# eBox_ACdetect.net
KiCad netlist of a schematic drawn in Altium Designer
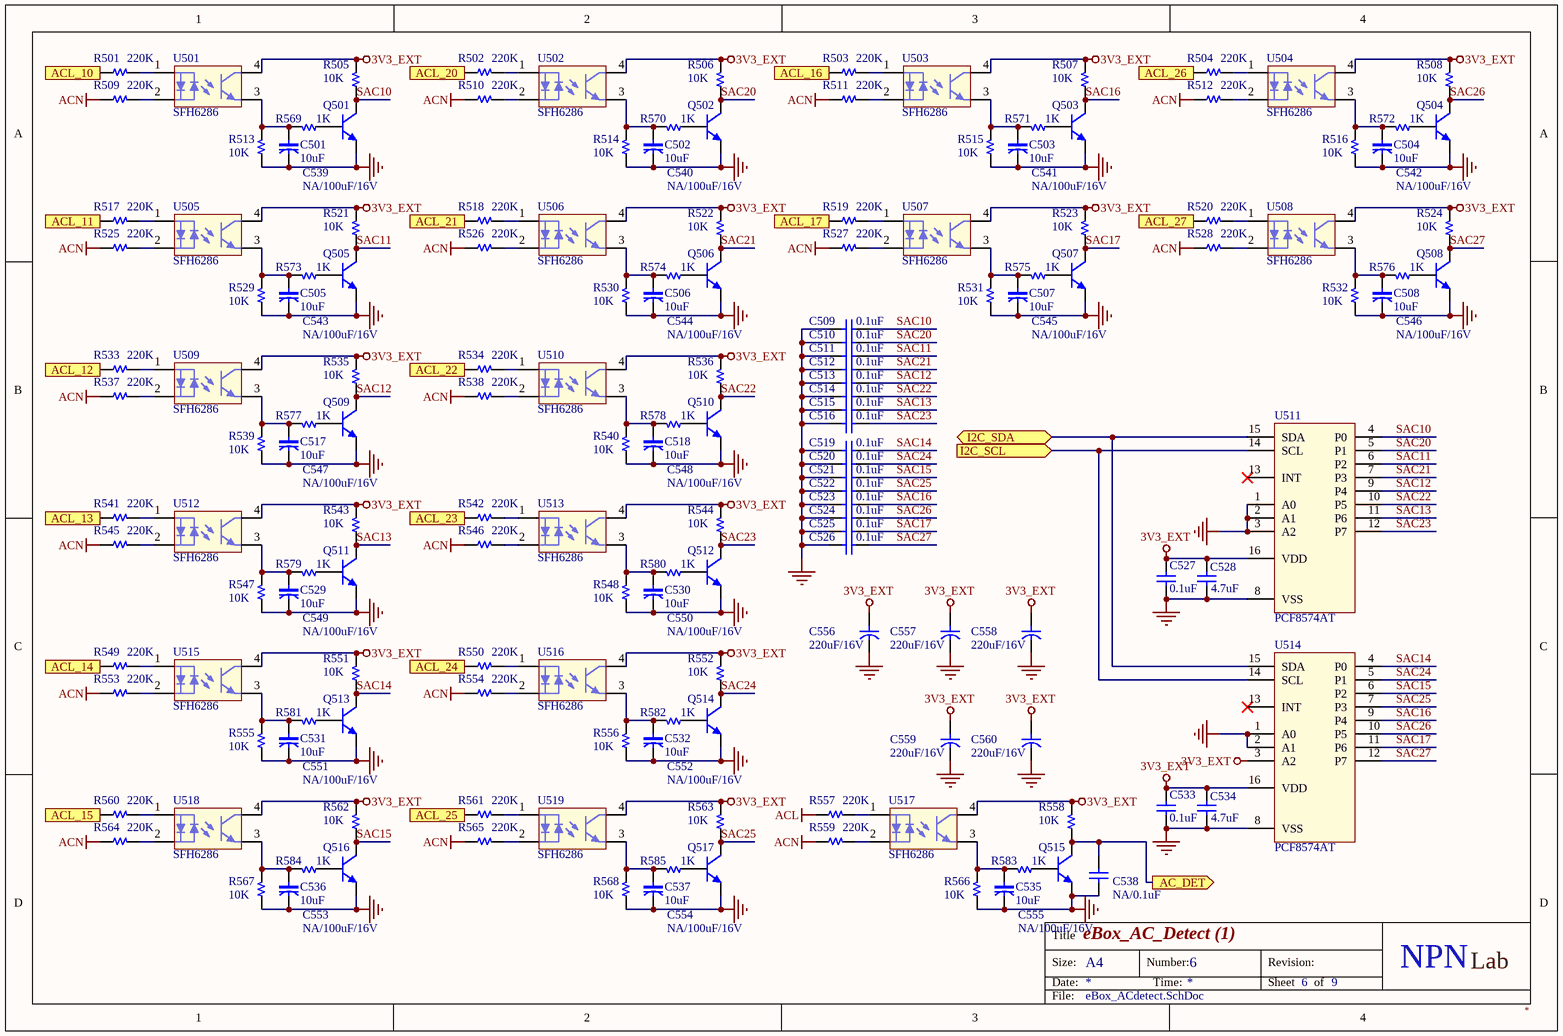
[diagram p0: eBox_ACdetect.SchDoc]

(export (version "E")
  (design (tool "Eeschema 10.0.6"))
  (components
    (comp (ref "C501")
      (value "10uF")
      (footprint "C 0805")
      (description "CAP CER 0.1UF 50V X7R 0805")
      (libsource (lib "chipfc_altium_libs") (part "Capacitor NP"))
    )
    (comp (ref "C502")
      (value "10uF")
      (footprint "C 0805")
      (description "CAP CER 0.1UF 50V X7R 0805")
      (libsource (lib "chipfc_altium_libs") (part "Capacitor NP"))
    )
    (comp (ref "C503")
      (value "10uF")
      (footprint "C 0805")
      (description "CAP CER 0.1UF 50V X7R 0805")
      (libsource (lib "chipfc_altium_libs") (part "Capacitor NP"))
    )
    (comp (ref "C504")
      (value "10uF")
      (footprint "C 0805")
      (description "CAP CER 0.1UF 50V X7R 0805")
      (libsource (lib "chipfc_altium_libs") (part "Capacitor NP"))
    )
    (comp (ref "C505")
      (value "10uF")
      (footprint "C 0805")
      (description "CAP CER 0.1UF 50V X7R 0805")
      (libsource (lib "chipfc_altium_libs") (part "Capacitor NP"))
    )
    (comp (ref "C506")
      (value "10uF")
      (footprint "C 0805")
      (description "CAP CER 0.1UF 50V X7R 0805")
      (libsource (lib "chipfc_altium_libs") (part "Capacitor NP"))
    )
    (comp (ref "C507")
      (value "10uF")
      (footprint "C 0805")
      (description "CAP CER 0.1UF 50V X7R 0805")
      (libsource (lib "chipfc_altium_libs") (part "Capacitor NP"))
    )
    (comp (ref "C508")
      (value "10uF")
      (footprint "C 0805")
      (description "CAP CER 0.1UF 50V X7R 0805")
      (libsource (lib "chipfc_altium_libs") (part "Capacitor NP"))
    )
    (comp (ref "C509")
      (value "0.1uF")
      (footprint "C 0805")
      (description "CAP CER 0.1UF 50V X7R 0805")
      (libsource (lib "chipfc_altium_libs") (part "Capacitor NP"))
    )
    (comp (ref "C510")
      (value "0.1uF")
      (footprint "C 0805")
      (description "CAP CER 0.1UF 50V X7R 0805")
      (libsource (lib "chipfc_altium_libs") (part "Capacitor NP"))
    )
    (comp (ref "C511")
      (value "0.1uF")
      (footprint "C 0805")
      (description "CAP CER 0.1UF 50V X7R 0805")
      (libsource (lib "chipfc_altium_libs") (part "Capacitor NP"))
    )
    (comp (ref "C512")
      (value "0.1uF")
      (footprint "C 0805")
      (description "CAP CER 0.1UF 50V X7R 0805")
      (libsource (lib "chipfc_altium_libs") (part "Capacitor NP"))
    )
    (comp (ref "C513")
      (value "0.1uF")
      (footprint "C 0805")
      (description "CAP CER 0.1UF 50V X7R 0805")
      (libsource (lib "chipfc_altium_libs") (part "Capacitor NP"))
    )
    (comp (ref "C514")
      (value "0.1uF")
      (footprint "C 0805")
      (description "CAP CER 0.1UF 50V X7R 0805")
      (libsource (lib "chipfc_altium_libs") (part "Capacitor NP"))
    )
    (comp (ref "C515")
      (value "0.1uF")
      (footprint "C 0805")
      (description "CAP CER 0.1UF 50V X7R 0805")
      (libsource (lib "chipfc_altium_libs") (part "Capacitor NP"))
    )
    (comp (ref "C516")
      (value "0.1uF")
      (footprint "C 0805")
      (description "CAP CER 0.1UF 50V X7R 0805")
      (libsource (lib "chipfc_altium_libs") (part "Capacitor NP"))
    )
    (comp (ref "C517")
      (value "10uF")
      (footprint "C 0805")
      (description "CAP CER 0.1UF 50V X7R 0805")
      (libsource (lib "chipfc_altium_libs") (part "Capacitor NP"))
    )
    (comp (ref "C518")
      (value "10uF")
      (footprint "C 0805")
      (description "CAP CER 0.1UF 50V X7R 0805")
      (libsource (lib "chipfc_altium_libs") (part "Capacitor NP"))
    )
    (comp (ref "C519")
      (value "0.1uF")
      (footprint "C 0805")
      (description "CAP CER 0.1UF 50V X7R 0805")
      (libsource (lib "chipfc_altium_libs") (part "Capacitor NP"))
    )
    (comp (ref "C520")
      (value "0.1uF")
      (footprint "C 0805")
      (description "CAP CER 0.1UF 50V X7R 0805")
      (libsource (lib "chipfc_altium_libs") (part "Capacitor NP"))
    )
    (comp (ref "C521")
      (value "0.1uF")
      (footprint "C 0805")
      (description "CAP CER 0.1UF 50V X7R 0805")
      (libsource (lib "chipfc_altium_libs") (part "Capacitor NP"))
    )
    (comp (ref "C522")
      (value "0.1uF")
      (footprint "C 0805")
      (description "CAP CER 0.1UF 50V X7R 0805")
      (libsource (lib "chipfc_altium_libs") (part "Capacitor NP"))
    )
    (comp (ref "C523")
      (value "0.1uF")
      (footprint "C 0805")
      (description "CAP CER 0.1UF 50V X7R 0805")
      (libsource (lib "chipfc_altium_libs") (part "Capacitor NP"))
    )
    (comp (ref "C524")
      (value "0.1uF")
      (footprint "C 0805")
      (description "CAP CER 0.1UF 50V X7R 0805")
      (libsource (lib "chipfc_altium_libs") (part "Capacitor NP"))
    )
    (comp (ref "C525")
      (value "0.1uF")
      (footprint "C 0805")
      (description "CAP CER 0.1UF 50V X7R 0805")
      (libsource (lib "chipfc_altium_libs") (part "Capacitor NP"))
    )
    (comp (ref "C526")
      (value "0.1uF")
      (footprint "C 0805")
      (description "CAP CER 0.1UF 50V X7R 0805")
      (libsource (lib "chipfc_altium_libs") (part "Capacitor NP"))
    )
    (comp (ref "C527")
      (value "0.1uF")
      (footprint "C 0603")
      (description "CAP CER 0.1UF 50V X7R 0603")
      (libsource (lib "chipfc_altium_libs") (part "Capacitor NP"))
    )
    (comp (ref "C528")
      (value "4.7uF")
      (footprint "C 0603")
      (description "CAP CER 4.7UF 50V X7R 0603")
      (libsource (lib "chipfc_altium_libs") (part "Capacitor NP"))
    )
    (comp (ref "C529")
      (value "10uF")
      (footprint "C 0805")
      (description "CAP CER 0.1UF 50V X7R 0805")
      (libsource (lib "chipfc_altium_libs") (part "Capacitor NP"))
    )
    (comp (ref "C530")
      (value "10uF")
      (footprint "C 0805")
      (description "CAP CER 0.1UF 50V X7R 0805")
      (libsource (lib "chipfc_altium_libs") (part "Capacitor NP"))
    )
    (comp (ref "C531")
      (value "10uF")
      (footprint "C 0805")
      (description "CAP CER 0.1UF 50V X7R 0805")
      (libsource (lib "chipfc_altium_libs") (part "Capacitor NP"))
    )
    (comp (ref "C532")
      (value "10uF")
      (footprint "C 0805")
      (description "CAP CER 0.1UF 50V X7R 0805")
      (libsource (lib "chipfc_altium_libs") (part "Capacitor NP"))
    )
    (comp (ref "C533")
      (value "0.1uF")
      (footprint "C 0603")
      (description "CAP CER 0.1UF 50V X7R 0603")
      (libsource (lib "chipfc_altium_libs") (part "Capacitor NP"))
    )
    (comp (ref "C534")
      (value "4.7uF")
      (footprint "C 0603")
      (description "CAP CER 4.7UF 50V X7R 0603")
      (libsource (lib "chipfc_altium_libs") (part "Capacitor NP"))
    )
    (comp (ref "C535")
      (value "10uF")
      (footprint "C 0805")
      (description "CAP CER 0.1UF 50V X7R 0805")
      (libsource (lib "chipfc_altium_libs") (part "Capacitor NP"))
    )
    (comp (ref "C536")
      (value "10uF")
      (footprint "C 0805")
      (description "CAP CER 0.1UF 50V X7R 0805")
      (libsource (lib "chipfc_altium_libs") (part "Capacitor NP"))
    )
    (comp (ref "C537")
      (value "10uF")
      (footprint "C 0805")
      (description "CAP CER 0.1UF 50V X7R 0805")
      (libsource (lib "chipfc_altium_libs") (part "Capacitor NP"))
    )
    (comp (ref "C538")
      (value "NA/0.1uF")
      (footprint "C 0805")
      (description "CAP CER 0.1UF 50V X7R 0805")
      (libsource (lib "chipfc_altium_libs") (part "Capacitor NP"))
    )
    (comp (ref "C539")
      (value "NA/100uF/16V")
      (footprint "CYL/D.200/LS.75-D50H70P20")
      (description "CAP ALUM 100UF 20% 16V RADIAL")
      (libsource (lib "chipfc_altium_libs") (part "Capacitor"))
    )
    (comp (ref "C540")
      (value "NA/100uF/16V")
      (footprint "CYL/D.200/LS.75-D50H70P20")
      (description "CAP ALUM 100UF 20% 16V RADIAL")
      (libsource (lib "chipfc_altium_libs") (part "Capacitor"))
    )
    (comp (ref "C541")
      (value "NA/100uF/16V")
      (footprint "CYL/D.200/LS.75-D50H70P20")
      (description "CAP ALUM 100UF 20% 16V RADIAL")
      (libsource (lib "chipfc_altium_libs") (part "Capacitor"))
    )
    (comp (ref "C542")
      (value "NA/100uF/16V")
      (footprint "CYL/D.200/LS.75-D50H70P20")
      (description "CAP ALUM 100UF 20% 16V RADIAL")
      (libsource (lib "chipfc_altium_libs") (part "Capacitor"))
    )
    (comp (ref "C543")
      (value "NA/100uF/16V")
      (footprint "CYL/D.200/LS.75-D50H70P20")
      (description "CAP ALUM 100UF 20% 16V RADIAL")
      (libsource (lib "chipfc_altium_libs") (part "Capacitor"))
    )
    (comp (ref "C544")
      (value "NA/100uF/16V")
      (footprint "CYL/D.200/LS.75-D50H70P20")
      (description "CAP ALUM 100UF 20% 16V RADIAL")
      (libsource (lib "chipfc_altium_libs") (part "Capacitor"))
    )
    (comp (ref "C545")
      (value "NA/100uF/16V")
      (footprint "CYL/D.200/LS.75-D50H70P20")
      (description "CAP ALUM 100UF 20% 16V RADIAL")
      (libsource (lib "chipfc_altium_libs") (part "Capacitor"))
    )
    (comp (ref "C546")
      (value "NA/100uF/16V")
      (footprint "CYL/D.200/LS.75-D50H70P20")
      (description "CAP ALUM 100UF 20% 16V RADIAL")
      (libsource (lib "chipfc_altium_libs") (part "Capacitor"))
    )
    (comp (ref "C547")
      (value "NA/100uF/16V")
      (footprint "CYL/D.200/LS.75-D50H70P20")
      (description "CAP ALUM 100UF 20% 16V RADIAL")
      (libsource (lib "chipfc_altium_libs") (part "Capacitor"))
    )
    (comp (ref "C548")
      (value "NA/100uF/16V")
      (footprint "CYL/D.200/LS.75-D50H70P20")
      (description "CAP ALUM 100UF 20% 16V RADIAL")
      (libsource (lib "chipfc_altium_libs") (part "Capacitor"))
    )
    (comp (ref "C549")
      (value "NA/100uF/16V")
      (footprint "CYL/D.200/LS.75-D50H70P20")
      (description "CAP ALUM 100UF 20% 16V RADIAL")
      (libsource (lib "chipfc_altium_libs") (part "Capacitor"))
    )
    (comp (ref "C550")
      (value "NA/100uF/16V")
      (footprint "CYL/D.200/LS.75-D50H70P20")
      (description "CAP ALUM 100UF 20% 16V RADIAL")
      (libsource (lib "chipfc_altium_libs") (part "Capacitor"))
    )
    (comp (ref "C551")
      (value "NA/100uF/16V")
      (footprint "CYL/D.200/LS.75-D50H70P20")
      (description "CAP ALUM 100UF 20% 16V RADIAL")
      (libsource (lib "chipfc_altium_libs") (part "Capacitor"))
    )
    (comp (ref "C552")
      (value "NA/100uF/16V")
      (footprint "CYL/D.200/LS.75-D50H70P20")
      (description "CAP ALUM 100UF 20% 16V RADIAL")
      (libsource (lib "chipfc_altium_libs") (part "Capacitor"))
    )
    (comp (ref "C553")
      (value "NA/100uF/16V")
      (footprint "CYL/D.200/LS.75-D50H70P20")
      (description "CAP ALUM 100UF 20% 16V RADIAL")
      (libsource (lib "chipfc_altium_libs") (part "Capacitor"))
    )
    (comp (ref "C554")
      (value "NA/100uF/16V")
      (footprint "CYL/D.200/LS.75-D50H70P20")
      (description "CAP ALUM 100UF 20% 16V RADIAL")
      (libsource (lib "chipfc_altium_libs") (part "Capacitor"))
    )
    (comp (ref "C555")
      (value "NA/100uF/16V")
      (footprint "CYL/D.200/LS.75-D50H70P20")
      (description "CAP ALUM 100UF 20% 16V RADIAL")
      (libsource (lib "chipfc_altium_libs") (part "Capacitor"))
    )
    (comp (ref "C556")
      (value "220uF/16V")
      (footprint "CYL/D.250/LS.100-D63H70P25")
      (description "CAP ALUM 220UF 20% 16V RADIAL")
      (libsource (lib "") (part "Capacitor_1"))
    )
    (comp (ref "C557")
      (value "220uF/16V")
      (footprint "CYL/D.250/LS.100-D63H70P25")
      (description "CAP ALUM 220UF 20% 16V RADIAL")
      (libsource (lib "") (part "Capacitor_1"))
    )
    (comp (ref "C558")
      (value "220uF/16V")
      (footprint "CYL/D.250/LS.100-D63H70P25")
      (description "CAP ALUM 220UF 20% 16V RADIAL")
      (libsource (lib "") (part "Capacitor_1"))
    )
    (comp (ref "C559")
      (value "220uF/16V")
      (footprint "CYL/D.250/LS.100-D63H70P25")
      (description "CAP ALUM 220UF 20% 16V RADIAL")
      (libsource (lib "") (part "Capacitor_1"))
    )
    (comp (ref "C560")
      (value "220uF/16V")
      (footprint "CYL/D.250/LS.100-D63H70P25")
      (description "CAP ALUM 220UF 20% 16V RADIAL")
      (libsource (lib "") (part "Capacitor_1"))
    )
    (comp (ref "Q501")
      (value "MMBT3904LT1G")
      (footprint "SOT-23")
      (description "TRANS NPN 40V 0.2A SOT23")
      (libsource (lib "chipfc_altium_libs") (part "Transistor NPN"))
    )
    (comp (ref "Q502")
      (value "MMBT3904LT1G")
      (footprint "SOT-23")
      (description "TRANS NPN 40V 0.2A SOT23")
      (libsource (lib "chipfc_altium_libs") (part "Transistor NPN"))
    )
    (comp (ref "Q503")
      (value "MMBT3904LT1G")
      (footprint "SOT-23")
      (description "TRANS NPN 40V 0.2A SOT23")
      (libsource (lib "chipfc_altium_libs") (part "Transistor NPN"))
    )
    (comp (ref "Q504")
      (value "MMBT3904LT1G")
      (footprint "SOT-23")
      (description "TRANS NPN 40V 0.2A SOT23")
      (libsource (lib "chipfc_altium_libs") (part "Transistor NPN"))
    )
    (comp (ref "Q505")
      (value "MMBT3904LT1G")
      (footprint "SOT-23")
      (description "TRANS NPN 40V 0.2A SOT23")
      (libsource (lib "chipfc_altium_libs") (part "Transistor NPN"))
    )
    (comp (ref "Q506")
      (value "MMBT3904LT1G")
      (footprint "SOT-23")
      (description "TRANS NPN 40V 0.2A SOT23")
      (libsource (lib "chipfc_altium_libs") (part "Transistor NPN"))
    )
    (comp (ref "Q507")
      (value "MMBT3904LT1G")
      (footprint "SOT-23")
      (description "TRANS NPN 40V 0.2A SOT23")
      (libsource (lib "chipfc_altium_libs") (part "Transistor NPN"))
    )
    (comp (ref "Q508")
      (value "MMBT3904LT1G")
      (footprint "SOT-23")
      (description "TRANS NPN 40V 0.2A SOT23")
      (libsource (lib "chipfc_altium_libs") (part "Transistor NPN"))
    )
    (comp (ref "Q509")
      (value "MMBT3904LT1G")
      (footprint "SOT-23")
      (description "TRANS NPN 40V 0.2A SOT23")
      (libsource (lib "chipfc_altium_libs") (part "Transistor NPN"))
    )
    (comp (ref "Q510")
      (value "MMBT3904LT1G")
      (footprint "SOT-23")
      (description "TRANS NPN 40V 0.2A SOT23")
      (libsource (lib "chipfc_altium_libs") (part "Transistor NPN"))
    )
    (comp (ref "Q511")
      (value "MMBT3904LT1G")
      (footprint "SOT-23")
      (description "TRANS NPN 40V 0.2A SOT23")
      (libsource (lib "chipfc_altium_libs") (part "Transistor NPN"))
    )
    (comp (ref "Q512")
      (value "MMBT3904LT1G")
      (footprint "SOT-23")
      (description "TRANS NPN 40V 0.2A SOT23")
      (libsource (lib "chipfc_altium_libs") (part "Transistor NPN"))
    )
    (comp (ref "Q513")
      (value "MMBT3904LT1G")
      (footprint "SOT-23")
      (description "TRANS NPN 40V 0.2A SOT23")
      (libsource (lib "chipfc_altium_libs") (part "Transistor NPN"))
    )
    (comp (ref "Q514")
      (value "MMBT3904LT1G")
      (footprint "SOT-23")
      (description "TRANS NPN 40V 0.2A SOT23")
      (libsource (lib "chipfc_altium_libs") (part "Transistor NPN"))
    )
    (comp (ref "Q515")
      (value "MMBT3904LT1G")
      (footprint "SOT-23")
      (description "TRANS NPN 40V 0.2A SOT23")
      (libsource (lib "chipfc_altium_libs") (part "Transistor NPN"))
    )
    (comp (ref "Q516")
      (value "MMBT3904LT1G")
      (footprint "SOT-23")
      (description "TRANS NPN 40V 0.2A SOT23")
      (libsource (lib "chipfc_altium_libs") (part "Transistor NPN"))
    )
    (comp (ref "Q517")
      (value "MMBT3904LT1G")
      (footprint "SOT-23")
      (description "TRANS NPN 40V 0.2A SOT23")
      (libsource (lib "chipfc_altium_libs") (part "Transistor NPN"))
    )
    (comp (ref "R501")
      (value "220K")
      (footprint "R 0805")
      (description "RES SMD 220K OHM 1% 1/8W 0805")
      (libsource (lib "chipfc_altium_libs") (part "Resistor"))
    )
    (comp (ref "R502")
      (value "220K")
      (footprint "R 0805")
      (description "RES SMD 220K OHM 1% 1/8W 0805")
      (libsource (lib "chipfc_altium_libs") (part "Resistor"))
    )
    (comp (ref "R503")
      (value "220K")
      (footprint "R 0805")
      (description "RES SMD 220K OHM 1% 1/8W 0805")
      (libsource (lib "chipfc_altium_libs") (part "Resistor"))
    )
    (comp (ref "R504")
      (value "220K")
      (footprint "R 0805")
      (description "RES SMD 220K OHM 1% 1/8W 0805")
      (libsource (lib "chipfc_altium_libs") (part "Resistor"))
    )
    (comp (ref "R505")
      (value "10K")
      (footprint "R 0805")
      (description "RES SMD 10K OHM 1% 1/8W 0805")
      (libsource (lib "chipfc_altium_libs") (part "Resistor"))
    )
    (comp (ref "R506")
      (value "10K")
      (footprint "R 0805")
      (description "RES SMD 10K OHM 1% 1/8W 0805")
      (libsource (lib "chipfc_altium_libs") (part "Resistor"))
    )
    (comp (ref "R507")
      (value "10K")
      (footprint "R 0805")
      (description "RES SMD 10K OHM 1% 1/8W 0805")
      (libsource (lib "chipfc_altium_libs") (part "Resistor"))
    )
    (comp (ref "R508")
      (value "10K")
      (footprint "R 0805")
      (description "RES SMD 10K OHM 1% 1/8W 0805")
      (libsource (lib "chipfc_altium_libs") (part "Resistor"))
    )
    (comp (ref "R509")
      (value "220K")
      (footprint "R 0805")
      (description "RES SMD 220K OHM 1% 1/8W 0805")
      (libsource (lib "chipfc_altium_libs") (part "Resistor"))
    )
    (comp (ref "R510")
      (value "220K")
      (footprint "R 0805")
      (description "RES SMD 220K OHM 1% 1/8W 0805")
      (libsource (lib "chipfc_altium_libs") (part "Resistor"))
    )
    (comp (ref "R511")
      (value "220K")
      (footprint "R 0805")
      (description "RES SMD 220K OHM 1% 1/8W 0805")
      (libsource (lib "chipfc_altium_libs") (part "Resistor"))
    )
    (comp (ref "R512")
      (value "220K")
      (footprint "R 0805")
      (description "RES SMD 220K OHM 1% 1/8W 0805")
      (libsource (lib "chipfc_altium_libs") (part "Resistor"))
    )
    (comp (ref "R513")
      (value "10K")
      (footprint "R 0805")
      (description "RES SMD 10K OHM 1% 1/8W 0805")
      (libsource (lib "chipfc_altium_libs") (part "Resistor"))
    )
    (comp (ref "R514")
      (value "10K")
      (footprint "R 0805")
      (description "RES SMD 10K OHM 1% 1/8W 0805")
      (libsource (lib "chipfc_altium_libs") (part "Resistor"))
    )
    (comp (ref "R515")
      (value "10K")
      (footprint "R 0805")
      (description "RES SMD 10K OHM 1% 1/8W 0805")
      (libsource (lib "chipfc_altium_libs") (part "Resistor"))
    )
    (comp (ref "R516")
      (value "10K")
      (footprint "R 0805")
      (description "RES SMD 10K OHM 1% 1/8W 0805")
      (libsource (lib "chipfc_altium_libs") (part "Resistor"))
    )
    (comp (ref "R517")
      (value "220K")
      (footprint "R 0805")
      (description "RES SMD 220K OHM 1% 1/8W 0805")
      (libsource (lib "chipfc_altium_libs") (part "Resistor"))
    )
    (comp (ref "R518")
      (value "220K")
      (footprint "R 0805")
      (description "RES SMD 220K OHM 1% 1/8W 0805")
      (libsource (lib "chipfc_altium_libs") (part "Resistor"))
    )
    (comp (ref "R519")
      (value "220K")
      (footprint "R 0805")
      (description "RES SMD 220K OHM 1% 1/8W 0805")
      (libsource (lib "chipfc_altium_libs") (part "Resistor"))
    )
    (comp (ref "R520")
      (value "220K")
      (footprint "R 0805")
      (description "RES SMD 220K OHM 1% 1/8W 0805")
      (libsource (lib "chipfc_altium_libs") (part "Resistor"))
    )
    (comp (ref "R521")
      (value "10K")
      (footprint "R 0805")
      (description "RES SMD 10K OHM 1% 1/8W 0805")
      (libsource (lib "chipfc_altium_libs") (part "Resistor"))
    )
    (comp (ref "R522")
      (value "10K")
      (footprint "R 0805")
      (description "RES SMD 10K OHM 1% 1/8W 0805")
      (libsource (lib "chipfc_altium_libs") (part "Resistor"))
    )
    (comp (ref "R523")
      (value "10K")
      (footprint "R 0805")
      (description "RES SMD 10K OHM 1% 1/8W 0805")
      (libsource (lib "chipfc_altium_libs") (part "Resistor"))
    )
    (comp (ref "R524")
      (value "10K")
      (footprint "R 0805")
      (description "RES SMD 10K OHM 1% 1/8W 0805")
      (libsource (lib "chipfc_altium_libs") (part "Resistor"))
    )
    (comp (ref "R525")
      (value "220K")
      (footprint "R 0805")
      (description "RES SMD 220K OHM 1% 1/8W 0805")
      (libsource (lib "chipfc_altium_libs") (part "Resistor"))
    )
    (comp (ref "R526")
      (value "220K")
      (footprint "R 0805")
      (description "RES SMD 220K OHM 1% 1/8W 0805")
      (libsource (lib "chipfc_altium_libs") (part "Resistor"))
    )
    (comp (ref "R527")
      (value "220K")
      (footprint "R 0805")
      (description "RES SMD 220K OHM 1% 1/8W 0805")
      (libsource (lib "chipfc_altium_libs") (part "Resistor"))
    )
    (comp (ref "R528")
      (value "220K")
      (footprint "R 0805")
      (description "RES SMD 220K OHM 1% 1/8W 0805")
      (libsource (lib "chipfc_altium_libs") (part "Resistor"))
    )
    (comp (ref "R529")
      (value "10K")
      (footprint "R 0805")
      (description "RES SMD 10K OHM 1% 1/8W 0805")
      (libsource (lib "chipfc_altium_libs") (part "Resistor"))
    )
    (comp (ref "R530")
      (value "10K")
      (footprint "R 0805")
      (description "RES SMD 10K OHM 1% 1/8W 0805")
      (libsource (lib "chipfc_altium_libs") (part "Resistor"))
    )
    (comp (ref "R531")
      (value "10K")
      (footprint "R 0805")
      (description "RES SMD 10K OHM 1% 1/8W 0805")
      (libsource (lib "chipfc_altium_libs") (part "Resistor"))
    )
    (comp (ref "R532")
      (value "10K")
      (footprint "R 0805")
      (description "RES SMD 10K OHM 1% 1/8W 0805")
      (libsource (lib "chipfc_altium_libs") (part "Resistor"))
    )
    (comp (ref "R533")
      (value "220K")
      (footprint "R 0805")
      (description "RES SMD 220K OHM 1% 1/8W 0805")
      (libsource (lib "chipfc_altium_libs") (part "Resistor"))
    )
    (comp (ref "R534")
      (value "220K")
      (footprint "R 0805")
      (description "RES SMD 220K OHM 1% 1/8W 0805")
      (libsource (lib "chipfc_altium_libs") (part "Resistor"))
    )
    (comp (ref "R535")
      (value "10K")
      (footprint "R 0805")
      (description "RES SMD 10K OHM 1% 1/8W 0805")
      (libsource (lib "chipfc_altium_libs") (part "Resistor"))
    )
    (comp (ref "R536")
      (value "10K")
      (footprint "R 0805")
      (description "RES SMD 10K OHM 1% 1/8W 0805")
      (libsource (lib "chipfc_altium_libs") (part "Resistor"))
    )
    (comp (ref "R537")
      (value "220K")
      (footprint "R 0805")
      (description "RES SMD 220K OHM 1% 1/8W 0805")
      (libsource (lib "chipfc_altium_libs") (part "Resistor"))
    )
    (comp (ref "R538")
      (value "220K")
      (footprint "R 0805")
      (description "RES SMD 220K OHM 1% 1/8W 0805")
      (libsource (lib "chipfc_altium_libs") (part "Resistor"))
    )
    (comp (ref "R539")
      (value "10K")
      (footprint "R 0805")
      (description "RES SMD 10K OHM 1% 1/8W 0805")
      (libsource (lib "chipfc_altium_libs") (part "Resistor"))
    )
    (comp (ref "R540")
      (value "10K")
      (footprint "R 0805")
      (description "RES SMD 10K OHM 1% 1/8W 0805")
      (libsource (lib "chipfc_altium_libs") (part "Resistor"))
    )
    (comp (ref "R541")
      (value "220K")
      (footprint "R 0805")
      (description "RES SMD 220K OHM 1% 1/8W 0805")
      (libsource (lib "chipfc_altium_libs") (part "Resistor"))
    )
    (comp (ref "R542")
      (value "220K")
      (footprint "R 0805")
      (description "RES SMD 220K OHM 1% 1/8W 0805")
      (libsource (lib "chipfc_altium_libs") (part "Resistor"))
    )
    (comp (ref "R543")
      (value "10K")
      (footprint "R 0805")
      (description "RES SMD 10K OHM 1% 1/8W 0805")
      (libsource (lib "chipfc_altium_libs") (part "Resistor"))
    )
    (comp (ref "R544")
      (value "10K")
      (footprint "R 0805")
      (description "RES SMD 10K OHM 1% 1/8W 0805")
      (libsource (lib "chipfc_altium_libs") (part "Resistor"))
    )
    (comp (ref "R545")
      (value "220K")
      (footprint "R 0805")
      (description "RES SMD 220K OHM 1% 1/8W 0805")
      (libsource (lib "chipfc_altium_libs") (part "Resistor"))
    )
    (comp (ref "R546")
      (value "220K")
      (footprint "R 0805")
      (description "RES SMD 220K OHM 1% 1/8W 0805")
      (libsource (lib "chipfc_altium_libs") (part "Resistor"))
    )
    (comp (ref "R547")
      (value "10K")
      (footprint "R 0805")
      (description "RES SMD 10K OHM 1% 1/8W 0805")
      (libsource (lib "chipfc_altium_libs") (part "Resistor"))
    )
    (comp (ref "R548")
      (value "10K")
      (footprint "R 0805")
      (description "RES SMD 10K OHM 1% 1/8W 0805")
      (libsource (lib "chipfc_altium_libs") (part "Resistor"))
    )
    (comp (ref "R549")
      (value "220K")
      (footprint "R 0805")
      (description "RES SMD 220K OHM 1% 1/8W 0805")
      (libsource (lib "chipfc_altium_libs") (part "Resistor"))
    )
    (comp (ref "R550")
      (value "220K")
      (footprint "R 0805")
      (description "RES SMD 220K OHM 1% 1/8W 0805")
      (libsource (lib "chipfc_altium_libs") (part "Resistor"))
    )
    (comp (ref "R551")
      (value "10K")
      (footprint "R 0805")
      (description "RES SMD 10K OHM 1% 1/8W 0805")
      (libsource (lib "chipfc_altium_libs") (part "Resistor"))
    )
    (comp (ref "R552")
      (value "10K")
      (footprint "R 0805")
      (description "RES SMD 10K OHM 1% 1/8W 0805")
      (libsource (lib "chipfc_altium_libs") (part "Resistor"))
    )
    (comp (ref "R553")
      (value "220K")
      (footprint "R 0805")
      (description "RES SMD 220K OHM 1% 1/8W 0805")
      (libsource (lib "chipfc_altium_libs") (part "Resistor"))
    )
    (comp (ref "R554")
      (value "220K")
      (footprint "R 0805")
      (description "RES SMD 220K OHM 1% 1/8W 0805")
      (libsource (lib "chipfc_altium_libs") (part "Resistor"))
    )
    (comp (ref "R555")
      (value "10K")
      (footprint "R 0805")
      (description "RES SMD 10K OHM 1% 1/8W 0805")
      (libsource (lib "chipfc_altium_libs") (part "Resistor"))
    )
    (comp (ref "R556")
      (value "10K")
      (footprint "R 0805")
      (description "RES SMD 10K OHM 1% 1/8W 0805")
      (libsource (lib "chipfc_altium_libs") (part "Resistor"))
    )
    (comp (ref "R557")
      (value "220K")
      (footprint "R 0805")
      (description "RES SMD 220K OHM 1% 1/8W 0805")
      (libsource (lib "chipfc_altium_libs") (part "Resistor"))
    )
    (comp (ref "R558")
      (value "10K")
      (footprint "R 0805")
      (description "RES SMD 10K OHM 1% 1/8W 0805")
      (libsource (lib "chipfc_altium_libs") (part "Resistor"))
    )
    (comp (ref "R559")
      (value "220K")
      (footprint "R 0805")
      (description "RES SMD 220K OHM 1% 1/8W 0805")
      (libsource (lib "chipfc_altium_libs") (part "Resistor"))
    )
    (comp (ref "R560")
      (value "220K")
      (footprint "R 0805")
      (description "RES SMD 220K OHM 1% 1/8W 0805")
      (libsource (lib "chipfc_altium_libs") (part "Resistor"))
    )
    (comp (ref "R561")
      (value "220K")
      (footprint "R 0805")
      (description "RES SMD 220K OHM 1% 1/8W 0805")
      (libsource (lib "chipfc_altium_libs") (part "Resistor"))
    )
    (comp (ref "R562")
      (value "10K")
      (footprint "R 0805")
      (description "RES SMD 10K OHM 1% 1/8W 0805")
      (libsource (lib "chipfc_altium_libs") (part "Resistor"))
    )
    (comp (ref "R563")
      (value "10K")
      (footprint "R 0805")
      (description "RES SMD 10K OHM 1% 1/8W 0805")
      (libsource (lib "chipfc_altium_libs") (part "Resistor"))
    )
    (comp (ref "R564")
      (value "220K")
      (footprint "R 0805")
      (description "RES SMD 220K OHM 1% 1/8W 0805")
      (libsource (lib "chipfc_altium_libs") (part "Resistor"))
    )
    (comp (ref "R565")
      (value "220K")
      (footprint "R 0805")
      (description "RES SMD 220K OHM 1% 1/8W 0805")
      (libsource (lib "chipfc_altium_libs") (part "Resistor"))
    )
    (comp (ref "R566")
      (value "10K")
      (footprint "R 0805")
      (description "RES SMD 10K OHM 1% 1/8W 0805")
      (libsource (lib "chipfc_altium_libs") (part "Resistor"))
    )
    (comp (ref "R567")
      (value "10K")
      (footprint "R 0805")
      (description "RES SMD 10K OHM 1% 1/8W 0805")
      (libsource (lib "chipfc_altium_libs") (part "Resistor"))
    )
    (comp (ref "R568")
      (value "10K")
      (footprint "R 0805")
      (description "RES SMD 10K OHM 1% 1/8W 0805")
      (libsource (lib "chipfc_altium_libs") (part "Resistor"))
    )
    (comp (ref "R569")
      (value "1K")
      (footprint "R 0805")
      (description "RES SMD 1K OHM 5% 1/8W 0805")
      (libsource (lib "chipfc_altium_libs") (part "Resistor"))
    )
    (comp (ref "R570")
      (value "1K")
      (footprint "R 0805")
      (description "RES SMD 1K OHM 5% 1/8W 0805")
      (libsource (lib "chipfc_altium_libs") (part "Resistor"))
    )
    (comp (ref "R571")
      (value "1K")
      (footprint "R 0805")
      (description "RES SMD 1K OHM 5% 1/8W 0805")
      (libsource (lib "chipfc_altium_libs") (part "Resistor"))
    )
    (comp (ref "R572")
      (value "1K")
      (footprint "R 0805")
      (description "RES SMD 1K OHM 5% 1/8W 0805")
      (libsource (lib "chipfc_altium_libs") (part "Resistor"))
    )
    (comp (ref "R573")
      (value "1K")
      (footprint "R 0805")
      (description "RES SMD 1K OHM 5% 1/8W 0805")
      (libsource (lib "chipfc_altium_libs") (part "Resistor"))
    )
    (comp (ref "R574")
      (value "1K")
      (footprint "R 0805")
      (description "RES SMD 1K OHM 5% 1/8W 0805")
      (libsource (lib "chipfc_altium_libs") (part "Resistor"))
    )
    (comp (ref "R575")
      (value "1K")
      (footprint "R 0805")
      (description "RES SMD 1K OHM 5% 1/8W 0805")
      (libsource (lib "chipfc_altium_libs") (part "Resistor"))
    )
    (comp (ref "R576")
      (value "1K")
      (footprint "R 0805")
      (description "RES SMD 1K OHM 5% 1/8W 0805")
      (libsource (lib "chipfc_altium_libs") (part "Resistor"))
    )
    (comp (ref "R577")
      (value "1K")
      (footprint "R 0805")
      (description "RES SMD 1K OHM 5% 1/8W 0805")
      (libsource (lib "chipfc_altium_libs") (part "Resistor"))
    )
    (comp (ref "R578")
      (value "1K")
      (footprint "R 0805")
      (description "RES SMD 1K OHM 5% 1/8W 0805")
      (libsource (lib "chipfc_altium_libs") (part "Resistor"))
    )
    (comp (ref "R579")
      (value "1K")
      (footprint "R 0805")
      (description "RES SMD 1K OHM 5% 1/8W 0805")
      (libsource (lib "chipfc_altium_libs") (part "Resistor"))
    )
    (comp (ref "R580")
      (value "1K")
      (footprint "R 0805")
      (description "RES SMD 1K OHM 5% 1/8W 0805")
      (libsource (lib "chipfc_altium_libs") (part "Resistor"))
    )
    (comp (ref "R581")
      (value "1K")
      (footprint "R 0805")
      (description "RES SMD 1K OHM 5% 1/8W 0805")
      (libsource (lib "chipfc_altium_libs") (part "Resistor"))
    )
    (comp (ref "R582")
      (value "1K")
      (footprint "R 0805")
      (description "RES SMD 1K OHM 5% 1/8W 0805")
      (libsource (lib "chipfc_altium_libs") (part "Resistor"))
    )
    (comp (ref "R583")
      (value "1K")
      (footprint "R 0805")
      (description "RES SMD 1K OHM 5% 1/8W 0805")
      (libsource (lib "chipfc_altium_libs") (part "Resistor"))
    )
    (comp (ref "R584")
      (value "1K")
      (footprint "R 0805")
      (description "RES SMD 1K OHM 5% 1/8W 0805")
      (libsource (lib "chipfc_altium_libs") (part "Resistor"))
    )
    (comp (ref "R585")
      (value "1K")
      (footprint "R 0805")
      (description "RES SMD 1K OHM 5% 1/8W 0805")
      (libsource (lib "chipfc_altium_libs") (part "Resistor"))
    )
    (comp (ref "U501")
      (value "SFH6286")
      (footprint "SOP4 - SFH6286")
      (libsource (lib "chipfc_altium_libs") (part "SFH6286"))
    )
    (comp (ref "U502")
      (value "SFH6286")
      (footprint "SOP4 - SFH6286")
      (libsource (lib "chipfc_altium_libs") (part "SFH6286"))
    )
    (comp (ref "U503")
      (value "SFH6286")
      (footprint "SOP4 - SFH6286")
      (libsource (lib "chipfc_altium_libs") (part "SFH6286"))
    )
    (comp (ref "U504")
      (value "SFH6286")
      (footprint "SOP4 - SFH6286")
      (libsource (lib "chipfc_altium_libs") (part "SFH6286"))
    )
    (comp (ref "U505")
      (value "SFH6286")
      (footprint "SOP4 - SFH6286")
      (libsource (lib "chipfc_altium_libs") (part "SFH6286"))
    )
    (comp (ref "U506")
      (value "SFH6286")
      (footprint "SOP4 - SFH6286")
      (libsource (lib "chipfc_altium_libs") (part "SFH6286"))
    )
    (comp (ref "U507")
      (value "SFH6286")
      (footprint "SOP4 - SFH6286")
      (libsource (lib "chipfc_altium_libs") (part "SFH6286"))
    )
    (comp (ref "U508")
      (value "SFH6286")
      (footprint "SOP4 - SFH6286")
      (libsource (lib "chipfc_altium_libs") (part "SFH6286"))
    )
    (comp (ref "U509")
      (value "SFH6286")
      (footprint "SOP4 - SFH6286")
      (libsource (lib "chipfc_altium_libs") (part "SFH6286"))
    )
    (comp (ref "U510")
      (value "SFH6286")
      (footprint "SOP4 - SFH6286")
      (libsource (lib "chipfc_altium_libs") (part "SFH6286"))
    )
    (comp (ref "U511")
      (value "PCF8574AT")
      (footprint "SO16/PCF8574AT")
      (description "Remote 8-bit I/O expander for I2C-bus with interrupt")
      (fields (field (name "PART NO") "PCF8574AT/3"))
      (libsource (lib "chipfc_altium_libs") (part "PCF8574AT"))
    )
    (comp (ref "U512")
      (value "SFH6286")
      (footprint "SOP4 - SFH6286")
      (libsource (lib "chipfc_altium_libs") (part "SFH6286"))
    )
    (comp (ref "U513")
      (value "SFH6286")
      (footprint "SOP4 - SFH6286")
      (libsource (lib "chipfc_altium_libs") (part "SFH6286"))
    )
    (comp (ref "U514")
      (value "PCF8574AT")
      (footprint "SO16/PCF8574AT")
      (description "Remote 8-bit I/O expander for I2C-bus with interrupt")
      (fields (field (name "PART NO") "PCF8574AT/3"))
      (libsource (lib "chipfc_altium_libs") (part "PCF8574AT"))
    )
    (comp (ref "U515")
      (value "SFH6286")
      (footprint "SOP4 - SFH6286")
      (libsource (lib "chipfc_altium_libs") (part "SFH6286"))
    )
    (comp (ref "U516")
      (value "SFH6286")
      (footprint "SOP4 - SFH6286")
      (libsource (lib "chipfc_altium_libs") (part "SFH6286"))
    )
    (comp (ref "U517")
      (value "SFH6286")
      (footprint "SOP4 - SFH6286")
      (libsource (lib "chipfc_altium_libs") (part "SFH6286"))
    )
    (comp (ref "U518")
      (value "SFH6286")
      (footprint "SOP4 - SFH6286")
      (libsource (lib "chipfc_altium_libs") (part "SFH6286"))
    )
    (comp (ref "U519")
      (value "SFH6286")
      (footprint "SOP4 - SFH6286")
      (libsource (lib "chipfc_altium_libs") (part "SFH6286"))
    )
  )
  (nets
    (net (code "1") (name "/ACL_10") (class "Default")
      (node (ref "R501") (pin "1") (pinfunction "1_1") (pintype "passive"))
    )
    (net (code "2") (name "/ACL_11") (class "Default")
      (node (ref "R517") (pin "1") (pinfunction "1_1") (pintype "passive"))
    )
    (net (code "3") (name "/ACL_12") (class "Default")
      (node (ref "R533") (pin "1") (pinfunction "1_1") (pintype "passive"))
    )
    (net (code "4") (name "/ACL_13") (class "Default")
      (node (ref "R541") (pin "1") (pinfunction "1_1") (pintype "passive"))
    )
    (net (code "5") (name "/ACL_14") (class "Default")
      (node (ref "R549") (pin "1") (pinfunction "1_1") (pintype "passive"))
    )
    (net (code "6") (name "/ACL_15") (class "Default")
      (node (ref "R560") (pin "1") (pinfunction "1_1") (pintype "passive"))
    )
    (net (code "7") (name "/ACL_16") (class "Default")
      (node (ref "R503") (pin "1") (pinfunction "1_1") (pintype "passive"))
    )
    (net (code "8") (name "/ACL_17") (class "Default")
      (node (ref "R519") (pin "1") (pinfunction "1_1") (pintype "passive"))
    )
    (net (code "9") (name "/ACL_20") (class "Default")
      (node (ref "R502") (pin "1") (pinfunction "1_1") (pintype "passive"))
    )
    (net (code "10") (name "/ACL_21") (class "Default")
      (node (ref "R518") (pin "1") (pinfunction "1_1") (pintype "passive"))
    )
    (net (code "11") (name "/ACL_22") (class "Default")
      (node (ref "R534") (pin "1") (pinfunction "1_1") (pintype "passive"))
    )
    (net (code "12") (name "/ACL_23") (class "Default")
      (node (ref "R542") (pin "1") (pinfunction "1_1") (pintype "passive"))
    )
    (net (code "13") (name "/ACL_24") (class "Default")
      (node (ref "R550") (pin "1") (pinfunction "1_1") (pintype "passive"))
    )
    (net (code "14") (name "/ACL_25") (class "Default")
      (node (ref "R561") (pin "1") (pinfunction "1_1") (pintype "passive"))
    )
    (net (code "15") (name "/ACL_26") (class "Default")
      (node (ref "R504") (pin "1") (pinfunction "1_1") (pintype "passive"))
    )
    (net (code "16") (name "/ACL_27") (class "Default")
      (node (ref "R520") (pin "1") (pinfunction "1_1") (pintype "passive"))
    )
    (net (code "17") (name "/AC_DET") (class "Default")
      (node (ref "C538") (pin "2") (pinfunction "2_2") (pintype "passive"))
      (node (ref "Q515") (pin "3") (pinfunction "C_3") (pintype "passive"))
      (node (ref "R558") (pin "1") (pinfunction "1_1") (pintype "passive"))
    )
    (net (code "18") (name "/I2C_SCL") (class "Default")
      (node (ref "U511") (pin "14") (pinfunction "SCL_14") (pintype "passive"))
      (node (ref "U514") (pin "14") (pinfunction "SCL_14") (pintype "passive"))
    )
    (net (code "19") (name "/I2C_SDA") (class "Default")
      (node (ref "U511") (pin "15") (pinfunction "SDA_15") (pintype "passive"))
      (node (ref "U514") (pin "15") (pinfunction "SDA_15") (pintype "passive"))
    )
    (net (code "20") (name "/SAC10") (class "Default")
      (node (ref "C509") (pin "2") (pinfunction "2_2") (pintype "passive"))
      (node (ref "Q501") (pin "3") (pinfunction "C_3") (pintype "passive"))
      (node (ref "R505") (pin "1") (pinfunction "1_1") (pintype "passive"))
      (node (ref "U511") (pin "4") (pinfunction "P0_4") (pintype "passive"))
    )
    (net (code "21") (name "/SAC11") (class "Default")
      (node (ref "C511") (pin "2") (pinfunction "2_2") (pintype "passive"))
      (node (ref "Q505") (pin "3") (pinfunction "C_3") (pintype "passive"))
      (node (ref "R521") (pin "1") (pinfunction "1_1") (pintype "passive"))
      (node (ref "U511") (pin "6") (pinfunction "P2_6") (pintype "passive"))
    )
    (net (code "22") (name "/SAC12") (class "Default")
      (node (ref "C513") (pin "2") (pinfunction "2_2") (pintype "passive"))
      (node (ref "Q509") (pin "3") (pinfunction "C_3") (pintype "passive"))
      (node (ref "R535") (pin "1") (pinfunction "1_1") (pintype "passive"))
      (node (ref "U511") (pin "9") (pinfunction "P4_9") (pintype "passive"))
    )
    (net (code "23") (name "/SAC13") (class "Default")
      (node (ref "C515") (pin "2") (pinfunction "2_2") (pintype "passive"))
      (node (ref "Q511") (pin "3") (pinfunction "C_3") (pintype "passive"))
      (node (ref "R543") (pin "1") (pinfunction "1_1") (pintype "passive"))
      (node (ref "U511") (pin "11") (pinfunction "P6_11") (pintype "passive"))
    )
    (net (code "24") (name "/SAC14") (class "Default")
      (node (ref "C519") (pin "2") (pinfunction "2_2") (pintype "passive"))
      (node (ref "Q513") (pin "3") (pinfunction "C_3") (pintype "passive"))
      (node (ref "R551") (pin "1") (pinfunction "1_1") (pintype "passive"))
      (node (ref "U514") (pin "4") (pinfunction "P0_4") (pintype "passive"))
    )
    (net (code "25") (name "/SAC15") (class "Default")
      (node (ref "C521") (pin "2") (pinfunction "2_2") (pintype "passive"))
      (node (ref "Q516") (pin "3") (pinfunction "C_3") (pintype "passive"))
      (node (ref "R562") (pin "1") (pinfunction "1_1") (pintype "passive"))
      (node (ref "U514") (pin "6") (pinfunction "P2_6") (pintype "passive"))
    )
    (net (code "26") (name "/SAC16") (class "Default")
      (node (ref "C523") (pin "2") (pinfunction "2_2") (pintype "passive"))
      (node (ref "Q503") (pin "3") (pinfunction "C_3") (pintype "passive"))
      (node (ref "R507") (pin "1") (pinfunction "1_1") (pintype "passive"))
      (node (ref "U514") (pin "9") (pinfunction "P4_9") (pintype "passive"))
    )
    (net (code "27") (name "/SAC17") (class "Default")
      (node (ref "C525") (pin "2") (pinfunction "2_2") (pintype "passive"))
      (node (ref "Q507") (pin "3") (pinfunction "C_3") (pintype "passive"))
      (node (ref "R523") (pin "1") (pinfunction "1_1") (pintype "passive"))
      (node (ref "U514") (pin "11") (pinfunction "P6_11") (pintype "passive"))
    )
    (net (code "28") (name "/SAC20") (class "Default")
      (node (ref "C510") (pin "2") (pinfunction "2_2") (pintype "passive"))
      (node (ref "Q502") (pin "3") (pinfunction "C_3") (pintype "passive"))
      (node (ref "R506") (pin "1") (pinfunction "1_1") (pintype "passive"))
      (node (ref "U511") (pin "5") (pinfunction "P1_5") (pintype "passive"))
    )
    (net (code "29") (name "/SAC21") (class "Default")
      (node (ref "C512") (pin "2") (pinfunction "2_2") (pintype "passive"))
      (node (ref "Q506") (pin "3") (pinfunction "C_3") (pintype "passive"))
      (node (ref "R522") (pin "1") (pinfunction "1_1") (pintype "passive"))
      (node (ref "U511") (pin "7") (pinfunction "P3_7") (pintype "passive"))
    )
    (net (code "30") (name "/SAC22") (class "Default")
      (node (ref "C514") (pin "2") (pinfunction "2_2") (pintype "passive"))
      (node (ref "Q510") (pin "3") (pinfunction "C_3") (pintype "passive"))
      (node (ref "R536") (pin "1") (pinfunction "1_1") (pintype "passive"))
      (node (ref "U511") (pin "10") (pinfunction "P5_10") (pintype "passive"))
    )
    (net (code "31") (name "/SAC23") (class "Default")
      (node (ref "C516") (pin "2") (pinfunction "2_2") (pintype "passive"))
      (node (ref "Q512") (pin "3") (pinfunction "C_3") (pintype "passive"))
      (node (ref "R544") (pin "1") (pinfunction "1_1") (pintype "passive"))
      (node (ref "U511") (pin "12") (pinfunction "P7_12") (pintype "passive"))
    )
    (net (code "32") (name "/SAC24") (class "Default")
      (node (ref "C520") (pin "2") (pinfunction "2_2") (pintype "passive"))
      (node (ref "Q514") (pin "3") (pinfunction "C_3") (pintype "passive"))
      (node (ref "R552") (pin "1") (pinfunction "1_1") (pintype "passive"))
      (node (ref "U514") (pin "5") (pinfunction "P1_5") (pintype "passive"))
    )
    (net (code "33") (name "/SAC25") (class "Default")
      (node (ref "C522") (pin "2") (pinfunction "2_2") (pintype "passive"))
      (node (ref "Q517") (pin "3") (pinfunction "C_3") (pintype "passive"))
      (node (ref "R563") (pin "1") (pinfunction "1_1") (pintype "passive"))
      (node (ref "U514") (pin "7") (pinfunction "P3_7") (pintype "passive"))
    )
    (net (code "34") (name "/SAC26") (class "Default")
      (node (ref "C524") (pin "2") (pinfunction "2_2") (pintype "passive"))
      (node (ref "Q504") (pin "3") (pinfunction "C_3") (pintype "passive"))
      (node (ref "R508") (pin "1") (pinfunction "1_1") (pintype "passive"))
      (node (ref "U514") (pin "10") (pinfunction "P5_10") (pintype "passive"))
    )
    (net (code "35") (name "/SAC27") (class "Default")
      (node (ref "C526") (pin "2") (pinfunction "2_2") (pintype "passive"))
      (node (ref "Q508") (pin "3") (pinfunction "C_3") (pintype "passive"))
      (node (ref "R524") (pin "1") (pinfunction "1_1") (pintype "passive"))
      (node (ref "U514") (pin "12") (pinfunction "P7_12") (pintype "passive"))
    )
    (net (code "36") (name "3V3_EXT") (class "Default")
      (node (ref "C527") (pin "1") (pinfunction "1_1") (pintype "passive"))
      (node (ref "C528") (pin "1") (pinfunction "1_1") (pintype "passive"))
      (node (ref "C533") (pin "1") (pinfunction "1_1") (pintype "passive"))
      (node (ref "C534") (pin "1") (pinfunction "1_1") (pintype "passive"))
      (node (ref "C556") (pin "1") (pinfunction "1_1") (pintype "passive"))
      (node (ref "C557") (pin "1") (pinfunction "1_1") (pintype "passive"))
      (node (ref "C558") (pin "1") (pinfunction "1_1") (pintype "passive"))
      (node (ref "C559") (pin "1") (pinfunction "1_1") (pintype "passive"))
      (node (ref "C560") (pin "1") (pinfunction "1_1") (pintype "passive"))
      (node (ref "R505") (pin "2") (pinfunction "2_2") (pintype "passive"))
      (node (ref "R506") (pin "2") (pinfunction "2_2") (pintype "passive"))
      (node (ref "R507") (pin "2") (pinfunction "2_2") (pintype "passive"))
      (node (ref "R508") (pin "2") (pinfunction "2_2") (pintype "passive"))
      (node (ref "R521") (pin "2") (pinfunction "2_2") (pintype "passive"))
      (node (ref "R522") (pin "2") (pinfunction "2_2") (pintype "passive"))
      (node (ref "R523") (pin "2") (pinfunction "2_2") (pintype "passive"))
      (node (ref "R524") (pin "2") (pinfunction "2_2") (pintype "passive"))
      (node (ref "R535") (pin "2") (pinfunction "2_2") (pintype "passive"))
      (node (ref "R536") (pin "2") (pinfunction "2_2") (pintype "passive"))
      (node (ref "R543") (pin "2") (pinfunction "2_2") (pintype "passive"))
      (node (ref "R544") (pin "2") (pinfunction "2_2") (pintype "passive"))
      (node (ref "R551") (pin "2") (pinfunction "2_2") (pintype "passive"))
      (node (ref "R552") (pin "2") (pinfunction "2_2") (pintype "passive"))
      (node (ref "R558") (pin "2") (pinfunction "2_2") (pintype "passive"))
      (node (ref "R562") (pin "2") (pinfunction "2_2") (pintype "passive"))
      (node (ref "R563") (pin "2") (pinfunction "2_2") (pintype "passive"))
      (node (ref "U501") (pin "4") (pinfunction "C_4") (pintype "passive"))
      (node (ref "U502") (pin "4") (pinfunction "C_4") (pintype "passive"))
      (node (ref "U503") (pin "4") (pinfunction "C_4") (pintype "passive"))
      (node (ref "U504") (pin "4") (pinfunction "C_4") (pintype "passive"))
      (node (ref "U505") (pin "4") (pinfunction "C_4") (pintype "passive"))
      (node (ref "U506") (pin "4") (pinfunction "C_4") (pintype "passive"))
      (node (ref "U507") (pin "4") (pinfunction "C_4") (pintype "passive"))
      (node (ref "U508") (pin "4") (pinfunction "C_4") (pintype "passive"))
      (node (ref "U509") (pin "4") (pinfunction "C_4") (pintype "passive"))
      (node (ref "U510") (pin "4") (pinfunction "C_4") (pintype "passive"))
      (node (ref "U511") (pin "16") (pinfunction "VDD_16") (pintype "passive"))
      (node (ref "U512") (pin "4") (pinfunction "C_4") (pintype "passive"))
      (node (ref "U513") (pin "4") (pinfunction "C_4") (pintype "passive"))
      (node (ref "U514") (pin "16") (pinfunction "VDD_16") (pintype "passive"))
      (node (ref "U514") (pin "3") (pinfunction "A2_3") (pintype "passive"))
      (node (ref "U515") (pin "4") (pinfunction "C_4") (pintype "passive"))
      (node (ref "U516") (pin "4") (pinfunction "C_4") (pintype "passive"))
      (node (ref "U517") (pin "4") (pinfunction "C_4") (pintype "passive"))
      (node (ref "U518") (pin "4") (pinfunction "C_4") (pintype "passive"))
      (node (ref "U519") (pin "4") (pinfunction "C_4") (pintype "passive"))
    )
    (net (code "37") (name "ACL") (class "Default")
      (node (ref "R557") (pin "1") (pinfunction "1_1") (pintype "passive"))
    )
    (net (code "38") (name "ACN") (class "Default")
      (node (ref "R509") (pin "1") (pinfunction "1_1") (pintype "passive"))
      (node (ref "R510") (pin "1") (pinfunction "1_1") (pintype "passive"))
      (node (ref "R511") (pin "1") (pinfunction "1_1") (pintype "passive"))
      (node (ref "R512") (pin "1") (pinfunction "1_1") (pintype "passive"))
      (node (ref "R525") (pin "1") (pinfunction "1_1") (pintype "passive"))
      (node (ref "R526") (pin "1") (pinfunction "1_1") (pintype "passive"))
      (node (ref "R527") (pin "1") (pinfunction "1_1") (pintype "passive"))
      (node (ref "R528") (pin "1") (pinfunction "1_1") (pintype "passive"))
      (node (ref "R537") (pin "1") (pinfunction "1_1") (pintype "passive"))
      (node (ref "R538") (pin "1") (pinfunction "1_1") (pintype "passive"))
      (node (ref "R545") (pin "1") (pinfunction "1_1") (pintype "passive"))
      (node (ref "R546") (pin "1") (pinfunction "1_1") (pintype "passive"))
      (node (ref "R553") (pin "1") (pinfunction "1_1") (pintype "passive"))
      (node (ref "R554") (pin "1") (pinfunction "1_1") (pintype "passive"))
      (node (ref "R559") (pin "1") (pinfunction "1_1") (pintype "passive"))
      (node (ref "R564") (pin "1") (pinfunction "1_1") (pintype "passive"))
      (node (ref "R565") (pin "1") (pinfunction "1_1") (pintype "passive"))
    )
    (net (code "39") (name "GND") (class "Default")
      (node (ref "C501") (pin "2") (pinfunction "2_2") (pintype "passive"))
      (node (ref "C502") (pin "2") (pinfunction "2_2") (pintype "passive"))
      (node (ref "C503") (pin "2") (pinfunction "2_2") (pintype "passive"))
      (node (ref "C504") (pin "2") (pinfunction "2_2") (pintype "passive"))
      (node (ref "C505") (pin "2") (pinfunction "2_2") (pintype "passive"))
      (node (ref "C506") (pin "2") (pinfunction "2_2") (pintype "passive"))
      (node (ref "C507") (pin "2") (pinfunction "2_2") (pintype "passive"))
      (node (ref "C508") (pin "2") (pinfunction "2_2") (pintype "passive"))
      (node (ref "C509") (pin "1") (pinfunction "1_1") (pintype "passive"))
      (node (ref "C510") (pin "1") (pinfunction "1_1") (pintype "passive"))
      (node (ref "C511") (pin "1") (pinfunction "1_1") (pintype "passive"))
      (node (ref "C512") (pin "1") (pinfunction "1_1") (pintype "passive"))
      (node (ref "C513") (pin "1") (pinfunction "1_1") (pintype "passive"))
      (node (ref "C514") (pin "1") (pinfunction "1_1") (pintype "passive"))
      (node (ref "C515") (pin "1") (pinfunction "1_1") (pintype "passive"))
      (node (ref "C516") (pin "1") (pinfunction "1_1") (pintype "passive"))
      (node (ref "C517") (pin "2") (pinfunction "2_2") (pintype "passive"))
      (node (ref "C518") (pin "2") (pinfunction "2_2") (pintype "passive"))
      (node (ref "C519") (pin "1") (pinfunction "1_1") (pintype "passive"))
      (node (ref "C520") (pin "1") (pinfunction "1_1") (pintype "passive"))
      (node (ref "C521") (pin "1") (pinfunction "1_1") (pintype "passive"))
      (node (ref "C522") (pin "1") (pinfunction "1_1") (pintype "passive"))
      (node (ref "C523") (pin "1") (pinfunction "1_1") (pintype "passive"))
      (node (ref "C524") (pin "1") (pinfunction "1_1") (pintype "passive"))
      (node (ref "C525") (pin "1") (pinfunction "1_1") (pintype "passive"))
      (node (ref "C526") (pin "1") (pinfunction "1_1") (pintype "passive"))
      (node (ref "C527") (pin "2") (pinfunction "2_2") (pintype "passive"))
      (node (ref "C528") (pin "2") (pinfunction "2_2") (pintype "passive"))
      (node (ref "C529") (pin "2") (pinfunction "2_2") (pintype "passive"))
      (node (ref "C530") (pin "2") (pinfunction "2_2") (pintype "passive"))
      (node (ref "C531") (pin "2") (pinfunction "2_2") (pintype "passive"))
      (node (ref "C532") (pin "2") (pinfunction "2_2") (pintype "passive"))
      (node (ref "C533") (pin "2") (pinfunction "2_2") (pintype "passive"))
      (node (ref "C534") (pin "2") (pinfunction "2_2") (pintype "passive"))
      (node (ref "C535") (pin "2") (pinfunction "2_2") (pintype "passive"))
      (node (ref "C536") (pin "2") (pinfunction "2_2") (pintype "passive"))
      (node (ref "C537") (pin "2") (pinfunction "2_2") (pintype "passive"))
      (node (ref "C538") (pin "1") (pinfunction "1_1") (pintype "passive"))
      (node (ref "C539") (pin "2") (pinfunction "2_2") (pintype "passive"))
      (node (ref "C540") (pin "2") (pinfunction "2_2") (pintype "passive"))
      (node (ref "C541") (pin "2") (pinfunction "2_2") (pintype "passive"))
      (node (ref "C542") (pin "2") (pinfunction "2_2") (pintype "passive"))
      (node (ref "C543") (pin "2") (pinfunction "2_2") (pintype "passive"))
      (node (ref "C544") (pin "2") (pinfunction "2_2") (pintype "passive"))
      (node (ref "C545") (pin "2") (pinfunction "2_2") (pintype "passive"))
      (node (ref "C546") (pin "2") (pinfunction "2_2") (pintype "passive"))
      (node (ref "C547") (pin "2") (pinfunction "2_2") (pintype "passive"))
      (node (ref "C548") (pin "2") (pinfunction "2_2") (pintype "passive"))
      (node (ref "C549") (pin "2") (pinfunction "2_2") (pintype "passive"))
      (node (ref "C550") (pin "2") (pinfunction "2_2") (pintype "passive"))
      (node (ref "C551") (pin "2") (pinfunction "2_2") (pintype "passive"))
      (node (ref "C552") (pin "2") (pinfunction "2_2") (pintype "passive"))
      (node (ref "C553") (pin "2") (pinfunction "2_2") (pintype "passive"))
      (node (ref "C554") (pin "2") (pinfunction "2_2") (pintype "passive"))
      (node (ref "C555") (pin "2") (pinfunction "2_2") (pintype "passive"))
      (node (ref "C556") (pin "2") (pinfunction "2_2") (pintype "passive"))
      (node (ref "C557") (pin "2") (pinfunction "2_2") (pintype "passive"))
      (node (ref "C558") (pin "2") (pinfunction "2_2") (pintype "passive"))
      (node (ref "C559") (pin "2") (pinfunction "2_2") (pintype "passive"))
      (node (ref "C560") (pin "2") (pinfunction "2_2") (pintype "passive"))
      (node (ref "Q501") (pin "2") (pinfunction "E_2") (pintype "passive"))
      (node (ref "Q502") (pin "2") (pinfunction "E_2") (pintype "passive"))
      (node (ref "Q503") (pin "2") (pinfunction "E_2") (pintype "passive"))
      (node (ref "Q504") (pin "2") (pinfunction "E_2") (pintype "passive"))
      (node (ref "Q505") (pin "2") (pinfunction "E_2") (pintype "passive"))
      (node (ref "Q506") (pin "2") (pinfunction "E_2") (pintype "passive"))
      (node (ref "Q507") (pin "2") (pinfunction "E_2") (pintype "passive"))
      (node (ref "Q508") (pin "2") (pinfunction "E_2") (pintype "passive"))
      (node (ref "Q509") (pin "2") (pinfunction "E_2") (pintype "passive"))
      (node (ref "Q510") (pin "2") (pinfunction "E_2") (pintype "passive"))
      (node (ref "Q511") (pin "2") (pinfunction "E_2") (pintype "passive"))
      (node (ref "Q512") (pin "2") (pinfunction "E_2") (pintype "passive"))
      (node (ref "Q513") (pin "2") (pinfunction "E_2") (pintype "passive"))
      (node (ref "Q514") (pin "2") (pinfunction "E_2") (pintype "passive"))
      (node (ref "Q515") (pin "2") (pinfunction "E_2") (pintype "passive"))
      (node (ref "Q516") (pin "2") (pinfunction "E_2") (pintype "passive"))
      (node (ref "Q517") (pin "2") (pinfunction "E_2") (pintype "passive"))
      (node (ref "R513") (pin "1") (pinfunction "1_1") (pintype "passive"))
      (node (ref "R514") (pin "1") (pinfunction "1_1") (pintype "passive"))
      (node (ref "R515") (pin "1") (pinfunction "1_1") (pintype "passive"))
      (node (ref "R516") (pin "1") (pinfunction "1_1") (pintype "passive"))
      (node (ref "R529") (pin "1") (pinfunction "1_1") (pintype "passive"))
      (node (ref "R530") (pin "1") (pinfunction "1_1") (pintype "passive"))
      (node (ref "R531") (pin "1") (pinfunction "1_1") (pintype "passive"))
      (node (ref "R532") (pin "1") (pinfunction "1_1") (pintype "passive"))
      (node (ref "R539") (pin "1") (pinfunction "1_1") (pintype "passive"))
      (node (ref "R540") (pin "1") (pinfunction "1_1") (pintype "passive"))
      (node (ref "R547") (pin "1") (pinfunction "1_1") (pintype "passive"))
      (node (ref "R548") (pin "1") (pinfunction "1_1") (pintype "passive"))
      (node (ref "R555") (pin "1") (pinfunction "1_1") (pintype "passive"))
      (node (ref "R556") (pin "1") (pinfunction "1_1") (pintype "passive"))
      (node (ref "R566") (pin "1") (pinfunction "1_1") (pintype "passive"))
      (node (ref "R567") (pin "1") (pinfunction "1_1") (pintype "passive"))
      (node (ref "R568") (pin "1") (pinfunction "1_1") (pintype "passive"))
      (node (ref "U511") (pin "1") (pinfunction "A0_1") (pintype "passive"))
      (node (ref "U511") (pin "2") (pinfunction "A1_2") (pintype "passive"))
      (node (ref "U511") (pin "3") (pinfunction "A2_3") (pintype "passive"))
      (node (ref "U511") (pin "8") (pinfunction "VSS_8") (pintype "passive"))
      (node (ref "U514") (pin "1") (pinfunction "A0_1") (pintype "passive"))
      (node (ref "U514") (pin "2") (pinfunction "A1_2") (pintype "passive"))
      (node (ref "U514") (pin "8") (pinfunction "VSS_8") (pintype "passive"))
    )
    (net (code "40") (name "Net-(Q501-B)") (class "Default")
      (node (ref "Q501") (pin "1") (pinfunction "B_1") (pintype "passive"))
      (node (ref "R569") (pin "1") (pinfunction "1_1") (pintype "passive"))
    )
    (net (code "41") (name "Net-(Q502-B)") (class "Default")
      (node (ref "Q502") (pin "1") (pinfunction "B_1") (pintype "passive"))
      (node (ref "R570") (pin "1") (pinfunction "1_1") (pintype "passive"))
    )
    (net (code "42") (name "Net-(Q503-B)") (class "Default")
      (node (ref "Q503") (pin "1") (pinfunction "B_1") (pintype "passive"))
      (node (ref "R571") (pin "1") (pinfunction "1_1") (pintype "passive"))
    )
    (net (code "43") (name "Net-(Q504-B)") (class "Default")
      (node (ref "Q504") (pin "1") (pinfunction "B_1") (pintype "passive"))
      (node (ref "R572") (pin "1") (pinfunction "1_1") (pintype "passive"))
    )
    (net (code "44") (name "Net-(Q505-B)") (class "Default")
      (node (ref "Q505") (pin "1") (pinfunction "B_1") (pintype "passive"))
      (node (ref "R573") (pin "1") (pinfunction "1_1") (pintype "passive"))
    )
    (net (code "45") (name "Net-(Q506-B)") (class "Default")
      (node (ref "Q506") (pin "1") (pinfunction "B_1") (pintype "passive"))
      (node (ref "R574") (pin "1") (pinfunction "1_1") (pintype "passive"))
    )
    (net (code "46") (name "Net-(Q507-B)") (class "Default")
      (node (ref "Q507") (pin "1") (pinfunction "B_1") (pintype "passive"))
      (node (ref "R575") (pin "1") (pinfunction "1_1") (pintype "passive"))
    )
    (net (code "47") (name "Net-(Q508-B)") (class "Default")
      (node (ref "Q508") (pin "1") (pinfunction "B_1") (pintype "passive"))
      (node (ref "R576") (pin "1") (pinfunction "1_1") (pintype "passive"))
    )
    (net (code "48") (name "Net-(Q509-B)") (class "Default")
      (node (ref "Q509") (pin "1") (pinfunction "B_1") (pintype "passive"))
      (node (ref "R577") (pin "1") (pinfunction "1_1") (pintype "passive"))
    )
    (net (code "49") (name "Net-(Q510-B)") (class "Default")
      (node (ref "Q510") (pin "1") (pinfunction "B_1") (pintype "passive"))
      (node (ref "R578") (pin "1") (pinfunction "1_1") (pintype "passive"))
    )
    (net (code "50") (name "Net-(Q511-B)") (class "Default")
      (node (ref "Q511") (pin "1") (pinfunction "B_1") (pintype "passive"))
      (node (ref "R579") (pin "1") (pinfunction "1_1") (pintype "passive"))
    )
    (net (code "51") (name "Net-(Q512-B)") (class "Default")
      (node (ref "Q512") (pin "1") (pinfunction "B_1") (pintype "passive"))
      (node (ref "R580") (pin "1") (pinfunction "1_1") (pintype "passive"))
    )
    (net (code "52") (name "Net-(Q513-B)") (class "Default")
      (node (ref "Q513") (pin "1") (pinfunction "B_1") (pintype "passive"))
      (node (ref "R581") (pin "1") (pinfunction "1_1") (pintype "passive"))
    )
    (net (code "53") (name "Net-(Q514-B)") (class "Default")
      (node (ref "Q514") (pin "1") (pinfunction "B_1") (pintype "passive"))
      (node (ref "R582") (pin "1") (pinfunction "1_1") (pintype "passive"))
    )
    (net (code "54") (name "Net-(Q515-B)") (class "Default")
      (node (ref "Q515") (pin "1") (pinfunction "B_1") (pintype "passive"))
      (node (ref "R583") (pin "1") (pinfunction "1_1") (pintype "passive"))
    )
    (net (code "55") (name "Net-(Q516-B)") (class "Default")
      (node (ref "Q516") (pin "1") (pinfunction "B_1") (pintype "passive"))
      (node (ref "R584") (pin "1") (pinfunction "1_1") (pintype "passive"))
    )
    (net (code "56") (name "Net-(Q517-B)") (class "Default")
      (node (ref "Q517") (pin "1") (pinfunction "B_1") (pintype "passive"))
      (node (ref "R585") (pin "1") (pinfunction "1_1") (pintype "passive"))
    )
    (net (code "57") (name "Net-(U501-A{slash}C)") (class "Default")
      (node (ref "R501") (pin "2") (pinfunction "2_2") (pintype "passive"))
      (node (ref "U501") (pin "1") (pinfunction "A/C_1") (pintype "passive"))
    )
    (net (code "58") (name "Net-(U501-C{slash}A)") (class "Default")
      (node (ref "R509") (pin "2") (pinfunction "2_2") (pintype "passive"))
      (node (ref "U501") (pin "2") (pinfunction "C/A_2") (pintype "passive"))
    )
    (net (code "59") (name "Net-(U501-E)") (class "Default")
      (node (ref "C501") (pin "1") (pinfunction "1_1") (pintype "passive"))
      (node (ref "C539") (pin "1") (pinfunction "1_1") (pintype "passive"))
      (node (ref "R513") (pin "2") (pinfunction "2_2") (pintype "passive"))
      (node (ref "R569") (pin "2") (pinfunction "2_2") (pintype "passive"))
      (node (ref "U501") (pin "3") (pinfunction "E_3") (pintype "passive"))
    )
    (net (code "60") (name "Net-(U502-A{slash}C)") (class "Default")
      (node (ref "R502") (pin "2") (pinfunction "2_2") (pintype "passive"))
      (node (ref "U502") (pin "1") (pinfunction "A/C_1") (pintype "passive"))
    )
    (net (code "61") (name "Net-(U502-C{slash}A)") (class "Default")
      (node (ref "R510") (pin "2") (pinfunction "2_2") (pintype "passive"))
      (node (ref "U502") (pin "2") (pinfunction "C/A_2") (pintype "passive"))
    )
    (net (code "62") (name "Net-(U502-E)") (class "Default")
      (node (ref "C502") (pin "1") (pinfunction "1_1") (pintype "passive"))
      (node (ref "C540") (pin "1") (pinfunction "1_1") (pintype "passive"))
      (node (ref "R514") (pin "2") (pinfunction "2_2") (pintype "passive"))
      (node (ref "R570") (pin "2") (pinfunction "2_2") (pintype "passive"))
      (node (ref "U502") (pin "3") (pinfunction "E_3") (pintype "passive"))
    )
    (net (code "63") (name "Net-(U503-A{slash}C)") (class "Default")
      (node (ref "R503") (pin "2") (pinfunction "2_2") (pintype "passive"))
      (node (ref "U503") (pin "1") (pinfunction "A/C_1") (pintype "passive"))
    )
    (net (code "64") (name "Net-(U503-C{slash}A)") (class "Default")
      (node (ref "R511") (pin "2") (pinfunction "2_2") (pintype "passive"))
      (node (ref "U503") (pin "2") (pinfunction "C/A_2") (pintype "passive"))
    )
    (net (code "65") (name "Net-(U503-E)") (class "Default")
      (node (ref "C503") (pin "1") (pinfunction "1_1") (pintype "passive"))
      (node (ref "C541") (pin "1") (pinfunction "1_1") (pintype "passive"))
      (node (ref "R515") (pin "2") (pinfunction "2_2") (pintype "passive"))
      (node (ref "R571") (pin "2") (pinfunction "2_2") (pintype "passive"))
      (node (ref "U503") (pin "3") (pinfunction "E_3") (pintype "passive"))
    )
    (net (code "66") (name "Net-(U504-A{slash}C)") (class "Default")
      (node (ref "R504") (pin "2") (pinfunction "2_2") (pintype "passive"))
      (node (ref "U504") (pin "1") (pinfunction "A/C_1") (pintype "passive"))
    )
    (net (code "67") (name "Net-(U504-C{slash}A)") (class "Default")
      (node (ref "R512") (pin "2") (pinfunction "2_2") (pintype "passive"))
      (node (ref "U504") (pin "2") (pinfunction "C/A_2") (pintype "passive"))
    )
    (net (code "68") (name "Net-(U504-E)") (class "Default")
      (node (ref "C504") (pin "1") (pinfunction "1_1") (pintype "passive"))
      (node (ref "C542") (pin "1") (pinfunction "1_1") (pintype "passive"))
      (node (ref "R516") (pin "2") (pinfunction "2_2") (pintype "passive"))
      (node (ref "R572") (pin "2") (pinfunction "2_2") (pintype "passive"))
      (node (ref "U504") (pin "3") (pinfunction "E_3") (pintype "passive"))
    )
    (net (code "69") (name "Net-(U505-A{slash}C)") (class "Default")
      (node (ref "R517") (pin "2") (pinfunction "2_2") (pintype "passive"))
      (node (ref "U505") (pin "1") (pinfunction "A/C_1") (pintype "passive"))
    )
    (net (code "70") (name "Net-(U505-C{slash}A)") (class "Default")
      (node (ref "R525") (pin "2") (pinfunction "2_2") (pintype "passive"))
      (node (ref "U505") (pin "2") (pinfunction "C/A_2") (pintype "passive"))
    )
    (net (code "71") (name "Net-(U505-E)") (class "Default")
      (node (ref "C505") (pin "1") (pinfunction "1_1") (pintype "passive"))
      (node (ref "C543") (pin "1") (pinfunction "1_1") (pintype "passive"))
      (node (ref "R529") (pin "2") (pinfunction "2_2") (pintype "passive"))
      (node (ref "R573") (pin "2") (pinfunction "2_2") (pintype "passive"))
      (node (ref "U505") (pin "3") (pinfunction "E_3") (pintype "passive"))
    )
    (net (code "72") (name "Net-(U506-A{slash}C)") (class "Default")
      (node (ref "R518") (pin "2") (pinfunction "2_2") (pintype "passive"))
      (node (ref "U506") (pin "1") (pinfunction "A/C_1") (pintype "passive"))
    )
    (net (code "73") (name "Net-(U506-C{slash}A)") (class "Default")
      (node (ref "R526") (pin "2") (pinfunction "2_2") (pintype "passive"))
      (node (ref "U506") (pin "2") (pinfunction "C/A_2") (pintype "passive"))
    )
    (net (code "74") (name "Net-(U506-E)") (class "Default")
      (node (ref "C506") (pin "1") (pinfunction "1_1") (pintype "passive"))
      (node (ref "C544") (pin "1") (pinfunction "1_1") (pintype "passive"))
      (node (ref "R530") (pin "2") (pinfunction "2_2") (pintype "passive"))
      (node (ref "R574") (pin "2") (pinfunction "2_2") (pintype "passive"))
      (node (ref "U506") (pin "3") (pinfunction "E_3") (pintype "passive"))
    )
    (net (code "75") (name "Net-(U507-A{slash}C)") (class "Default")
      (node (ref "R519") (pin "2") (pinfunction "2_2") (pintype "passive"))
      (node (ref "U507") (pin "1") (pinfunction "A/C_1") (pintype "passive"))
    )
    (net (code "76") (name "Net-(U507-C{slash}A)") (class "Default")
      (node (ref "R527") (pin "2") (pinfunction "2_2") (pintype "passive"))
      (node (ref "U507") (pin "2") (pinfunction "C/A_2") (pintype "passive"))
    )
    (net (code "77") (name "Net-(U507-E)") (class "Default")
      (node (ref "C507") (pin "1") (pinfunction "1_1") (pintype "passive"))
      (node (ref "C545") (pin "1") (pinfunction "1_1") (pintype "passive"))
      (node (ref "R531") (pin "2") (pinfunction "2_2") (pintype "passive"))
      (node (ref "R575") (pin "2") (pinfunction "2_2") (pintype "passive"))
      (node (ref "U507") (pin "3") (pinfunction "E_3") (pintype "passive"))
    )
    (net (code "78") (name "Net-(U508-A{slash}C)") (class "Default")
      (node (ref "R520") (pin "2") (pinfunction "2_2") (pintype "passive"))
      (node (ref "U508") (pin "1") (pinfunction "A/C_1") (pintype "passive"))
    )
    (net (code "79") (name "Net-(U508-C{slash}A)") (class "Default")
      (node (ref "R528") (pin "2") (pinfunction "2_2") (pintype "passive"))
      (node (ref "U508") (pin "2") (pinfunction "C/A_2") (pintype "passive"))
    )
    (net (code "80") (name "Net-(U508-E)") (class "Default")
      (node (ref "C508") (pin "1") (pinfunction "1_1") (pintype "passive"))
      (node (ref "C546") (pin "1") (pinfunction "1_1") (pintype "passive"))
      (node (ref "R532") (pin "2") (pinfunction "2_2") (pintype "passive"))
      (node (ref "R576") (pin "2") (pinfunction "2_2") (pintype "passive"))
      (node (ref "U508") (pin "3") (pinfunction "E_3") (pintype "passive"))
    )
    (net (code "81") (name "Net-(U509-A{slash}C)") (class "Default")
      (node (ref "R533") (pin "2") (pinfunction "2_2") (pintype "passive"))
      (node (ref "U509") (pin "1") (pinfunction "A/C_1") (pintype "passive"))
    )
    (net (code "82") (name "Net-(U509-C{slash}A)") (class "Default")
      (node (ref "R537") (pin "2") (pinfunction "2_2") (pintype "passive"))
      (node (ref "U509") (pin "2") (pinfunction "C/A_2") (pintype "passive"))
    )
    (net (code "83") (name "Net-(U509-E)") (class "Default")
      (node (ref "C517") (pin "1") (pinfunction "1_1") (pintype "passive"))
      (node (ref "C547") (pin "1") (pinfunction "1_1") (pintype "passive"))
      (node (ref "R539") (pin "2") (pinfunction "2_2") (pintype "passive"))
      (node (ref "R577") (pin "2") (pinfunction "2_2") (pintype "passive"))
      (node (ref "U509") (pin "3") (pinfunction "E_3") (pintype "passive"))
    )
    (net (code "84") (name "Net-(U510-A{slash}C)") (class "Default")
      (node (ref "R534") (pin "2") (pinfunction "2_2") (pintype "passive"))
      (node (ref "U510") (pin "1") (pinfunction "A/C_1") (pintype "passive"))
    )
    (net (code "85") (name "Net-(U510-C{slash}A)") (class "Default")
      (node (ref "R538") (pin "2") (pinfunction "2_2") (pintype "passive"))
      (node (ref "U510") (pin "2") (pinfunction "C/A_2") (pintype "passive"))
    )
    (net (code "86") (name "Net-(U510-E)") (class "Default")
      (node (ref "C518") (pin "1") (pinfunction "1_1") (pintype "passive"))
      (node (ref "C548") (pin "1") (pinfunction "1_1") (pintype "passive"))
      (node (ref "R540") (pin "2") (pinfunction "2_2") (pintype "passive"))
      (node (ref "R578") (pin "2") (pinfunction "2_2") (pintype "passive"))
      (node (ref "U510") (pin "3") (pinfunction "E_3") (pintype "passive"))
    )
    (net (code "87") (name "Net-(U512-A{slash}C)") (class "Default")
      (node (ref "R541") (pin "2") (pinfunction "2_2") (pintype "passive"))
      (node (ref "U512") (pin "1") (pinfunction "A/C_1") (pintype "passive"))
    )
    (net (code "88") (name "Net-(U512-C{slash}A)") (class "Default")
      (node (ref "R545") (pin "2") (pinfunction "2_2") (pintype "passive"))
      (node (ref "U512") (pin "2") (pinfunction "C/A_2") (pintype "passive"))
    )
    (net (code "89") (name "Net-(U512-E)") (class "Default")
      (node (ref "C529") (pin "1") (pinfunction "1_1") (pintype "passive"))
      (node (ref "C549") (pin "1") (pinfunction "1_1") (pintype "passive"))
      (node (ref "R547") (pin "2") (pinfunction "2_2") (pintype "passive"))
      (node (ref "R579") (pin "2") (pinfunction "2_2") (pintype "passive"))
      (node (ref "U512") (pin "3") (pinfunction "E_3") (pintype "passive"))
    )
    (net (code "90") (name "Net-(U513-A{slash}C)") (class "Default")
      (node (ref "R542") (pin "2") (pinfunction "2_2") (pintype "passive"))
      (node (ref "U513") (pin "1") (pinfunction "A/C_1") (pintype "passive"))
    )
    (net (code "91") (name "Net-(U513-C{slash}A)") (class "Default")
      (node (ref "R546") (pin "2") (pinfunction "2_2") (pintype "passive"))
      (node (ref "U513") (pin "2") (pinfunction "C/A_2") (pintype "passive"))
    )
    (net (code "92") (name "Net-(U513-E)") (class "Default")
      (node (ref "C530") (pin "1") (pinfunction "1_1") (pintype "passive"))
      (node (ref "C550") (pin "1") (pinfunction "1_1") (pintype "passive"))
      (node (ref "R548") (pin "2") (pinfunction "2_2") (pintype "passive"))
      (node (ref "R580") (pin "2") (pinfunction "2_2") (pintype "passive"))
      (node (ref "U513") (pin "3") (pinfunction "E_3") (pintype "passive"))
    )
    (net (code "93") (name "Net-(U515-A{slash}C)") (class "Default")
      (node (ref "R549") (pin "2") (pinfunction "2_2") (pintype "passive"))
      (node (ref "U515") (pin "1") (pinfunction "A/C_1") (pintype "passive"))
    )
    (net (code "94") (name "Net-(U515-C{slash}A)") (class "Default")
      (node (ref "R553") (pin "2") (pinfunction "2_2") (pintype "passive"))
      (node (ref "U515") (pin "2") (pinfunction "C/A_2") (pintype "passive"))
    )
    (net (code "95") (name "Net-(U515-E)") (class "Default")
      (node (ref "C531") (pin "1") (pinfunction "1_1") (pintype "passive"))
      (node (ref "C551") (pin "1") (pinfunction "1_1") (pintype "passive"))
      (node (ref "R555") (pin "2") (pinfunction "2_2") (pintype "passive"))
      (node (ref "R581") (pin "2") (pinfunction "2_2") (pintype "passive"))
      (node (ref "U515") (pin "3") (pinfunction "E_3") (pintype "passive"))
    )
    (net (code "96") (name "Net-(U516-A{slash}C)") (class "Default")
      (node (ref "R550") (pin "2") (pinfunction "2_2") (pintype "passive"))
      (node (ref "U516") (pin "1") (pinfunction "A/C_1") (pintype "passive"))
    )
    (net (code "97") (name "Net-(U516-C{slash}A)") (class "Default")
      (node (ref "R554") (pin "2") (pinfunction "2_2") (pintype "passive"))
      (node (ref "U516") (pin "2") (pinfunction "C/A_2") (pintype "passive"))
    )
    (net (code "98") (name "Net-(U516-E)") (class "Default")
      (node (ref "C532") (pin "1") (pinfunction "1_1") (pintype "passive"))
      (node (ref "C552") (pin "1") (pinfunction "1_1") (pintype "passive"))
      (node (ref "R556") (pin "2") (pinfunction "2_2") (pintype "passive"))
      (node (ref "R582") (pin "2") (pinfunction "2_2") (pintype "passive"))
      (node (ref "U516") (pin "3") (pinfunction "E_3") (pintype "passive"))
    )
    (net (code "99") (name "Net-(U517-A{slash}C)") (class "Default")
      (node (ref "R557") (pin "2") (pinfunction "2_2") (pintype "passive"))
      (node (ref "U517") (pin "1") (pinfunction "A/C_1") (pintype "passive"))
    )
    (net (code "100") (name "Net-(U517-C{slash}A)") (class "Default")
      (node (ref "R559") (pin "2") (pinfunction "2_2") (pintype "passive"))
      (node (ref "U517") (pin "2") (pinfunction "C/A_2") (pintype "passive"))
    )
    (net (code "101") (name "Net-(U517-E)") (class "Default")
      (node (ref "C535") (pin "1") (pinfunction "1_1") (pintype "passive"))
      (node (ref "C555") (pin "1") (pinfunction "1_1") (pintype "passive"))
      (node (ref "R566") (pin "2") (pinfunction "2_2") (pintype "passive"))
      (node (ref "R583") (pin "2") (pinfunction "2_2") (pintype "passive"))
      (node (ref "U517") (pin "3") (pinfunction "E_3") (pintype "passive"))
    )
    (net (code "102") (name "Net-(U518-A{slash}C)") (class "Default")
      (node (ref "R560") (pin "2") (pinfunction "2_2") (pintype "passive"))
      (node (ref "U518") (pin "1") (pinfunction "A/C_1") (pintype "passive"))
    )
    (net (code "103") (name "Net-(U518-C{slash}A)") (class "Default")
      (node (ref "R564") (pin "2") (pinfunction "2_2") (pintype "passive"))
      (node (ref "U518") (pin "2") (pinfunction "C/A_2") (pintype "passive"))
    )
    (net (code "104") (name "Net-(U518-E)") (class "Default")
      (node (ref "C536") (pin "1") (pinfunction "1_1") (pintype "passive"))
      (node (ref "C553") (pin "1") (pinfunction "1_1") (pintype "passive"))
      (node (ref "R567") (pin "2") (pinfunction "2_2") (pintype "passive"))
      (node (ref "R584") (pin "2") (pinfunction "2_2") (pintype "passive"))
      (node (ref "U518") (pin "3") (pinfunction "E_3") (pintype "passive"))
    )
    (net (code "105") (name "Net-(U519-A{slash}C)") (class "Default")
      (node (ref "R561") (pin "2") (pinfunction "2_2") (pintype "passive"))
      (node (ref "U519") (pin "1") (pinfunction "A/C_1") (pintype "passive"))
    )
    (net (code "106") (name "Net-(U519-C{slash}A)") (class "Default")
      (node (ref "R565") (pin "2") (pinfunction "2_2") (pintype "passive"))
      (node (ref "U519") (pin "2") (pinfunction "C/A_2") (pintype "passive"))
    )
    (net (code "107") (name "Net-(U519-E)") (class "Default")
      (node (ref "C537") (pin "1") (pinfunction "1_1") (pintype "passive"))
      (node (ref "C554") (pin "1") (pinfunction "1_1") (pintype "passive"))
      (node (ref "R568") (pin "2") (pinfunction "2_2") (pintype "passive"))
      (node (ref "R585") (pin "2") (pinfunction "2_2") (pintype "passive"))
      (node (ref "U519") (pin "3") (pinfunction "E_3") (pintype "passive"))
    )
    (net (code "108") (name "unconnected-(U511-INT-Pad13)") (class "Default")
      (node (ref "U511") (pin "13") (pinfunction "INT_13") (pintype "passive+no_connect"))
    )
    (net (code "109") (name "unconnected-(U514-INT-Pad13)") (class "Default")
      (node (ref "U514") (pin "13") (pinfunction "INT_13") (pintype "passive+no_connect"))
    )
  )
)
